# Analog_amplifer_2.net
KiCad netlist of a schematic drawn in EAGLE
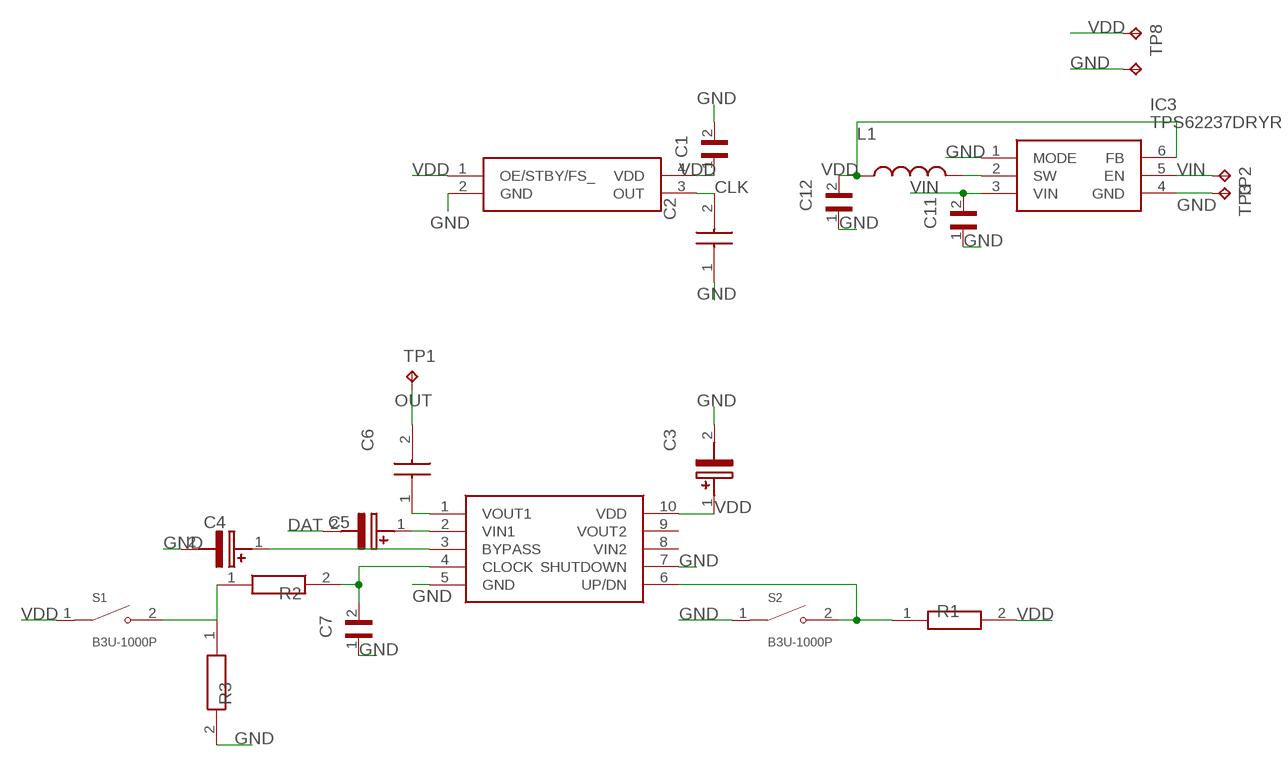
[diagram p0: schematic, sheet 1]
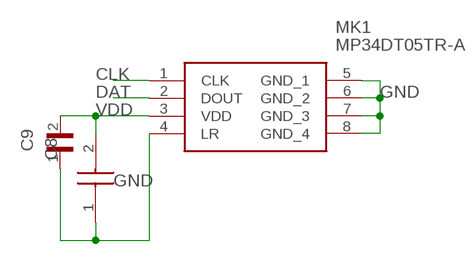
[diagram p1: schematic, sheet 2]

(export (version "E")
  (design (tool "Eeschema 10.0.6"))
  (components
    (comp (ref "C1")
      (value "GRM033C80J104KE15D")
      (footprint "eagle-import:CAPC0603X33N")
      (fields (field (name "DIGI-KEY_PART_NUMBER") "490-10390-1-ND") (field (name "MF") "Murata Electronics"))
      (libsource (lib "eagle-import") (part "GRM033C80J104KE15D"))
    )
    (comp (ref "C2")
      (value "GRM0115C1E5R0CE01L")
      (footprint "eagle-import:CAPC0201X14N")
      (fields (field (name "MOUSER_PART_NUMBER") "81-GRM0115C1E5RCE01L"))
      (libsource (lib "eagle-import") (part "GRM0115C1E5R0CE01L"))
    )
    (comp (ref "C3")
      (value "F380J105MUA")
      (footprint "eagle-import:CAPPC1106X60N")
      (fields (field (name "MOUSER_PART_NUMBER") "581-F380J105MUA"))
      (libsource (lib "eagle-import") (part "F380J105MUA"))
    )
    (comp (ref "C4")
      (value "F380J105MUA")
      (footprint "eagle-import:CAPPC1106X60N")
      (fields (field (name "MOUSER_PART_NUMBER") "581-F380J105MUA"))
      (libsource (lib "eagle-import") (part "F380J105MUA"))
    )
    (comp (ref "C5")
      (value "F380J105MUA")
      (footprint "eagle-import:CAPPC1106X60N")
      (fields (field (name "MOUSER_PART_NUMBER") "581-F380J105MUA"))
      (libsource (lib "eagle-import") (part "F380J105MUA"))
    )
    (comp (ref "C6")
      (value "GRM21BR60J107ME15L")
      (footprint "eagle-import:CAPC2012X145N")
      (fields (field (name "MOUSER_PART_NUMBER") "81-GRM21BR60J107ME5L"))
      (libsource (lib "eagle-import") (part "GRM21BR60J107ME15L"))
    )
    (comp (ref "C7")
      (value "GRM033C80J104KE15D")
      (footprint "eagle-import:CAPC0603X33N")
      (fields (field (name "DIGI-KEY_PART_NUMBER") "490-10390-1-ND") (field (name "MF") "Murata Electronics"))
      (libsource (lib "eagle-import") (part "GRM033C80J104KE15D"))
    )
    (comp (ref "C11")
      (value "GRM155R60J225KE95D")
      (footprint "eagle-import:CAPC1005X55N")
      (fields (field (name "DIGI-KEY_PART_NUMBER") "490-12532-1-ND") (field (name "MF") "Murata"))
      (libsource (lib "eagle-import") (part "GRM155R60J225KE95D"))
    )
    (comp (ref "C12")
      (value "GRM155R60J475ME47D")
      (footprint "eagle-import:CAPC1005X60N")
      (fields (field (name "DIGI-KEY_PART_NUMBER") "490-5915-1-ND") (field (name "MF") "Murata"))
      (libsource (lib "eagle-import") (part "GRM155R60J475ME47D"))
    )
    (comp (ref "IC1")
      (value "LM4811MM_NOPB")
      (footprint "eagle-import:SOP50P490X110-10N")
      (fields
        (field (name "ARROW_PART_NUMBER") "LM4811MM/NOPB")
        (field (name "MOUSER_PART_NUMBER") "926-LM4811MM/NOPB")
      )
      (libsource (lib "eagle-import") (part "LM4811MM_NOPB"))
    )
    (comp (ref "IC3")
      (value "TPS62237DRYR")
      (footprint "eagle-import:SON50P100X145X60-6N")
      (fields (field (name "MOUSER_PART_NUMBER") "595-TPS62237DRYR"))
      (libsource (lib "eagle-import") (part "TPS62237DRYR"))
    )
    (comp (ref "L1")
      (value "LQM21PN2R2MC0D")
      (footprint "eagle-import:INDC2012X55N")
      (fields (field (name "DIGI-KEY_PART_NUMBER") "490-4994-1-ND") (field (name "MF") "Murata"))
      (libsource (lib "eagle-import") (part "LQM21PN2R2MC0D"))
    )
    (comp (ref "R1")
      (value "RC0201FR-074K02L")
      (footprint "eagle-import:RESC0603X26N")
      (libsource (lib "eagle-import") (part "RC0201FR-074K02L"))
    )
    (comp (ref "R2")
      (value "RC0201FR-07100RL")
      (footprint "eagle-import:RESC0603X26N")
      (fields (field (name "MOUSER_PART_NUMBER") "603-RC0201FR-07100RL"))
      (libsource (lib "eagle-import") (part "RC0201FR-07100RL"))
    )
    (comp (ref "R3")
      (value "RC0201FR-07100RL")
      (footprint "eagle-import:RESC0603X26N")
      (fields (field (name "MOUSER_PART_NUMBER") "603-RC0201FR-07100RL"))
      (libsource (lib "eagle-import") (part "RC0201FR-07100RL"))
    )
    (comp (ref "S1")
      (value "B3U-1000P")
      (footprint "eagle-import:SW_B3U-1000P")
      (fields (field (name "DIGI-KEY_PART_NUMBER") "SW1020CT-ND") (field (name "MF") "Omron"))
      (libsource (lib "eagle-import") (part "B3U-1000P"))
    )
    (comp (ref "S2")
      (value "B3U-1000P")
      (footprint "eagle-import:SW_B3U-1000P")
      (fields (field (name "DIGI-KEY_PART_NUMBER") "SW1020CT-ND") (field (name "MF") "Omron"))
      (libsource (lib "eagle-import") (part "B3U-1000P"))
    )
    (comp (ref "TP1")
      (value "TPTP11R")
      (footprint "eagle-import:TP11R")
      (libsource (lib "eagle-import") (part "TPTP11R"))
    )
    (comp (ref "TP2")
      (value "TPTP11R")
      (footprint "eagle-import:TP11R")
      (libsource (lib "eagle-import") (part "TPTP11R"))
    )
    (comp (ref "TP3")
      (value "TPTP11R")
      (footprint "eagle-import:TP11R")
      (libsource (lib "eagle-import") (part "TPTP11R"))
    )
    (comp (ref "TP4")
      (value "TPTP11R")
      (footprint "eagle-import:TP11R")
      (libsource (lib "eagle-import") (part "TPTP11R"))
    )
    (comp (ref "TP8")
      (value "TPTP11R")
      (footprint "eagle-import:TP11R")
      (libsource (lib "eagle-import") (part "TPTP11R"))
    )
    (comp (ref "Y1")
      (value "DSC6053CE2A-003.0720")
      (footprint "eagle-import:DSC6053CE2A0030720")
      (libsource (lib "eagle-import") (part "DSC6053CE2A-003.0720"))
    )
    (comp (ref "C8")
      (value "C0402C105K9PACTU")
      (footprint "eagle-import:CAPC1005X55N")
      (fields (field (name "MOUSER_PART_NUMBER") "80-C0402C105K9P"))
      (libsource (lib "eagle-import") (part "C0402C105K9PACTU"))
    )
    (comp (ref "C9")
      (value "GRM033C80J104KE15D")
      (footprint "eagle-import:CAPC0603X33N")
      (fields (field (name "DIGI-KEY_PART_NUMBER") "490-10390-1-ND") (field (name "MF") "Murata Electronics"))
      (libsource (lib "eagle-import") (part "GRM033C80J104KE15D"))
    )
    (comp (ref "MK1")
      (value "MP34DT05TR-A")
      (footprint "eagle-import:MP34DT05TRA")
      (fields (field (name "MOUSER_PART_NUMBER") "511-MP34DT05TR-A"))
      (libsource (lib "eagle-import") (part "MP34DT05TR-A"))
    )
  )
  (nets
    (net (code "1") (name "CLK") (class "Default")
      (node (ref "C2") (pin "2") (pinfunction "2_2") (pintype "bidirectional"))
      (node (ref "MK1") (pin "1") (pinfunction "CLK_1") (pintype "bidirectional"))
      (node (ref "Y1") (pin "3") (pinfunction "OUT_3") (pintype "bidirectional"))
    )
    (net (code "2") (name "DAT") (class "Default")
      (node (ref "C5") (pin "2") (pinfunction "-_2") (pintype "bidirectional"))
      (node (ref "MK1") (pin "2") (pinfunction "DOUT_2") (pintype "bidirectional"))
    )
    (net (code "3") (name "GND") (class "Default")
      (node (ref "C1") (pin "2") (pinfunction "2_2") (pintype "passive"))
      (node (ref "C11") (pin "1") (pinfunction "1_1") (pintype "passive"))
      (node (ref "C12") (pin "1") (pinfunction "1_1") (pintype "passive"))
      (node (ref "C2") (pin "1") (pinfunction "1_1") (pintype "bidirectional"))
      (node (ref "C3") (pin "2") (pinfunction "-_2") (pintype "bidirectional"))
      (node (ref "C4") (pin "2") (pinfunction "-_2") (pintype "bidirectional"))
      (node (ref "C7") (pin "1") (pinfunction "1_1") (pintype "passive"))
      (node (ref "C8") (pin "1") (pinfunction "1_1") (pintype "bidirectional"))
      (node (ref "C9") (pin "1") (pinfunction "1_1") (pintype "passive"))
      (node (ref "IC1") (pin "5") (pinfunction "GND_5") (pintype "power_in"))
      (node (ref "IC1") (pin "7") (pinfunction "SHUTDOWN_7") (pintype "bidirectional"))
      (node (ref "IC3") (pin "1") (pinfunction "MODE_1") (pintype "bidirectional"))
      (node (ref "IC3") (pin "4") (pinfunction "GND_4") (pintype "bidirectional"))
      (node (ref "MK1") (pin "4") (pinfunction "LR_4") (pintype "bidirectional"))
      (node (ref "MK1") (pin "5") (pinfunction "GND_1_5") (pintype "bidirectional"))
      (node (ref "MK1") (pin "6") (pinfunction "GND_2_6") (pintype "bidirectional"))
      (node (ref "MK1") (pin "7") (pinfunction "GND_3_7") (pintype "bidirectional"))
      (node (ref "MK1") (pin "8") (pinfunction "GND_4_8") (pintype "bidirectional"))
      (node (ref "R3") (pin "2") (pinfunction "2_2") (pintype "bidirectional"))
      (node (ref "S2") (pin "1") (pinfunction "1_1") (pintype "passive"))
      (node (ref "TP3") (pin "TP") (pinfunction "TP_TP") (pintype "input"))
      (node (ref "TP4") (pin "TP") (pinfunction "TP_TP") (pintype "input"))
      (node (ref "Y1") (pin "2") (pinfunction "GND_2") (pintype "bidirectional"))
    )
    (net (code "4") (name "Net-(C4-+)") (class "Default")
      (node (ref "C4") (pin "1") (pinfunction "+_1") (pintype "bidirectional"))
      (node (ref "IC1") (pin "3") (pinfunction "BYPASS_3") (pintype "bidirectional"))
    )
    (net (code "5") (name "Net-(C5-+)") (class "Default")
      (node (ref "C5") (pin "1") (pinfunction "+_1") (pintype "bidirectional"))
      (node (ref "IC1") (pin "2") (pinfunction "VIN1_2") (pintype "input"))
    )
    (net (code "6") (name "Net-(IC1-CLOCK)") (class "Default")
      (node (ref "C7") (pin "2") (pinfunction "2_2") (pintype "passive"))
      (node (ref "IC1") (pin "4") (pinfunction "CLOCK_4") (pintype "input"))
      (node (ref "R2") (pin "2") (pinfunction "2_2") (pintype "bidirectional"))
    )
    (net (code "7") (name "Net-(IC1-UP{slash}DN)") (class "Default")
      (node (ref "IC1") (pin "6") (pinfunction "UP/DN_6") (pintype "bidirectional"))
      (node (ref "R1") (pin "1") (pinfunction "1_1") (pintype "bidirectional"))
      (node (ref "S2") (pin "2") (pinfunction "2_2") (pintype "passive"))
    )
    (net (code "8") (name "Net-(IC1-VOUT1)") (class "Default")
      (node (ref "C6") (pin "1") (pinfunction "1_1") (pintype "bidirectional"))
      (node (ref "IC1") (pin "1") (pinfunction "VOUT1_1") (pintype "output"))
    )
    (net (code "9") (name "Net-(IC3-SW)") (class "Default")
      (node (ref "IC3") (pin "2") (pinfunction "SW_2") (pintype "bidirectional"))
      (node (ref "L1") (pin "2") (pinfunction "2_2") (pintype "passive"))
    )
    (net (code "10") (name "Net-(R2-Pad1)") (class "Default")
      (node (ref "R2") (pin "1") (pinfunction "1_1") (pintype "bidirectional"))
      (node (ref "R3") (pin "1") (pinfunction "1_1") (pintype "bidirectional"))
      (node (ref "S1") (pin "2") (pinfunction "2_2") (pintype "passive"))
    )
    (net (code "11") (name "OUT") (class "Default")
      (node (ref "C6") (pin "2") (pinfunction "2_2") (pintype "bidirectional"))
      (node (ref "TP1") (pin "TP") (pinfunction "TP_TP") (pintype "input"))
    )
    (net (code "12") (name "VDD") (class "Default")
      (node (ref "C1") (pin "1") (pinfunction "1_1") (pintype "passive"))
      (node (ref "C12") (pin "2") (pinfunction "2_2") (pintype "passive"))
      (node (ref "C3") (pin "1") (pinfunction "+_1") (pintype "bidirectional"))
      (node (ref "C8") (pin "2") (pinfunction "2_2") (pintype "bidirectional"))
      (node (ref "C9") (pin "2") (pinfunction "2_2") (pintype "passive"))
      (node (ref "IC1") (pin "10") (pinfunction "VDD_10") (pintype "power_in"))
      (node (ref "IC3") (pin "6") (pinfunction "FB_6") (pintype "bidirectional"))
      (node (ref "L1") (pin "1") (pinfunction "1_1") (pintype "passive"))
      (node (ref "MK1") (pin "3") (pinfunction "VDD_3") (pintype "bidirectional"))
      (node (ref "R1") (pin "2") (pinfunction "2_2") (pintype "bidirectional"))
      (node (ref "S1") (pin "1") (pinfunction "1_1") (pintype "passive"))
      (node (ref "TP8") (pin "TP") (pinfunction "TP_TP") (pintype "input"))
      (node (ref "Y1") (pin "1") (pinfunction "OE/STBY/FS__1") (pintype "bidirectional"))
      (node (ref "Y1") (pin "4") (pinfunction "VDD_4") (pintype "bidirectional"))
    )
    (net (code "13") (name "VIN") (class "Default")
      (node (ref "C11") (pin "2") (pinfunction "2_2") (pintype "passive"))
      (node (ref "IC3") (pin "3") (pinfunction "VIN_3") (pintype "bidirectional"))
      (node (ref "IC3") (pin "5") (pinfunction "EN_5") (pintype "bidirectional"))
      (node (ref "TP2") (pin "TP") (pinfunction "TP_TP") (pintype "input"))
    )
    (net (code "14") (name "unconnected-(IC1-VIN2-Pad8)") (class "Default")
      (node (ref "IC1") (pin "8") (pinfunction "VIN2_8") (pintype "input"))
    )
    (net (code "15") (name "unconnected-(IC1-VOUT2-Pad9)") (class "Default")
      (node (ref "IC1") (pin "9") (pinfunction "VOUT2_9") (pintype "output"))
    )
  )
)
